# QSPI_NOR.net
KiCad netlist of a schematic drawn in Altium Designer
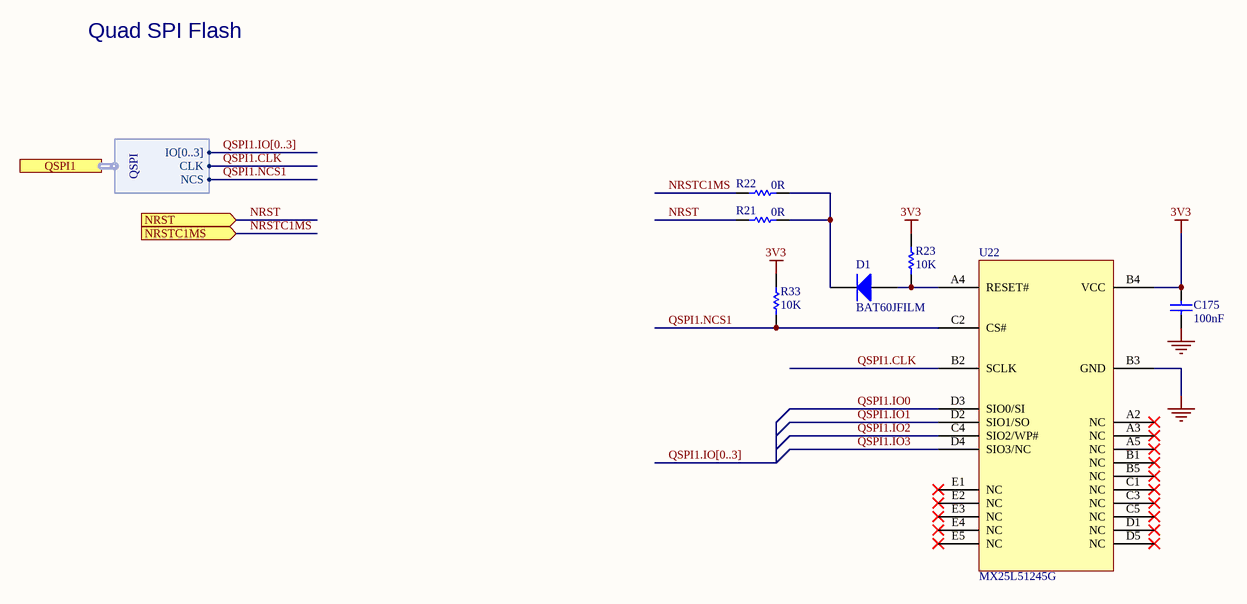
[diagram p0: QSPI_NOR.SchDoc]

(export (version "E")
  (design (tool "Eeschema 10.0.6"))
  (components
    (comp (ref "C175")
      (value "100nF")
      (footprint "MCD_PARTS:C0402")
      (description "Capacitor, MLCC, 100nF, 16V, X7R, +/-10%, 0402, T=0.5mm")
      (fields (field (name "INTERNAL_PART_NUMBER") "MCD-00006") (field (name "MANUFACTURER") "YAGEO"))
      (libsource (lib "MCD_PARTS_database") (part "Capacitor"))
    )
    (comp (ref "D1")
      (value "BAT60JFILM")
      (footprint "MCD_PARTS:DIO_SOD323")
      (fields
        (field (name "INTERNAL_PART_NUMBER") "MCD-00034")
        (field (name "BMS_PART_NUMBER") "9151097")
        (field (name "MANUFACTURER") "STMICROELECTRONICS")
      )
      (libsource (lib "MCD_PARTS_database") (part "BAT60JFILM"))
    )
    (comp (ref "R21")
      (value "0R")
      (footprint "MCD_PARTS:R0402")
      (description "Resistor,0R,0402,5%,1/16W")
      (fields
        (field (name "INTERNAL_PART_NUMBER") "MCD-00052")
        (field (name "MANUFACTURER_PART_NUMBER") "RC0402JR-070RL")
      )
      (libsource (lib "MCD_PARTS_database") (part "Resistor"))
    )
    (comp (ref "R22")
      (value "0R")
      (footprint "MCD_PARTS:R0402")
      (description "Resistor,0R,0402,5%,1/16W")
      (fields
        (field (name "INTERNAL_PART_NUMBER") "MCD-00052")
        (field (name "MANUFACTURER_PART_NUMBER") "RC0402JR-070RL")
      )
      (libsource (lib "MCD_PARTS_database") (part "Resistor"))
    )
    (comp (ref "R23")
      (value "10K")
      (footprint "MCD_PARTS:R0402")
      (description "Resistor,10K,0402,1%,1/16W")
      (fields
        (field (name "INTERNAL_PART_NUMBER") "MCD-00053")
        (field (name "MANUFACTURER_PART_NUMBER") "RC0402FR-0710KL")
        (field (name "PROVIDED_BY") "SUBCO")
      )
      (libsource (lib "MCD_PARTS_database") (part "Resistor"))
    )
    (comp (ref "R33")
      (value "10K")
      (footprint "MCD_PARTS:R0402")
      (description "Resistor,10K,0402,1%,1/16W")
      (fields
        (field (name "INTERNAL_PART_NUMBER") "MCD-00053")
        (field (name "MANUFACTURER_PART_NUMBER") "RC0402FR-0710KL")
        (field (name "PROVIDED_BY") "SUBCO")
      )
      (libsource (lib "MCD_PARTS_database") (part "Resistor"))
    )
    (comp (ref "U22")
      (value "MX25L51245G")
      (footprint "MCD_PARTS:ICC_BGA24_5X5-BALL-ARRAY_6X8_P1")
      (description "Memory,Serial-NOR,512Mb,3V")
      (fields
        (field (name "INTERNAL_PART_NUMBER") "MCD-00114")
        (field (name "MANUFACTURER") "MACRONIX")
        (field (name "PROVIDED_BY") "SUBCO")
      )
      (libsource (lib "MCD_PARTS_database") (part "MX25L51245G"))
    )
  )
  (nets
    (net (code "2") (name "/NRST") (class "Default")
      (node (ref "R21") (pin "1") (pinfunction "1_1") (pintype "passive"))
    )
    (net (code "3") (name "/NRSTC1MS") (class "Default")
      (node (ref "R22") (pin "1") (pinfunction "1_1") (pintype "passive"))
    )
    (net (code "4") (name "/QSPI1.CLK") (class "Default")
      (node (ref "U22") (pin "B2") (pinfunction "SCLK_B2") (pintype "passive"))
    )
    (net (code "5") (name "/QSPI1.IO0") (class "Default")
      (node (ref "U22") (pin "D3") (pinfunction "SIO0/SI_D3") (pintype "passive"))
    )
    (net (code "6") (name "/QSPI1.IO1") (class "Default")
      (node (ref "U22") (pin "D2") (pinfunction "SIO1/SO_D2") (pintype "passive"))
    )
    (net (code "7") (name "/QSPI1.IO2") (class "Default")
      (node (ref "U22") (pin "C4") (pinfunction "SIO2/WP#_C4") (pintype "passive"))
    )
    (net (code "8") (name "/QSPI1.IO3") (class "Default")
      (node (ref "U22") (pin "D4") (pinfunction "SIO3/NC_D4") (pintype "passive"))
    )
    (net (code "10") (name "/QSPI1.NCS1") (class "Default")
      (node (ref "R33") (pin "1") (pinfunction "1_1") (pintype "passive"))
      (node (ref "U22") (pin "C2") (pinfunction "CS#_C2") (pintype "passive"))
    )
    (net (code "12") (name "3V3") (class "Default")
      (node (ref "C175") (pin "2") (pinfunction "2_2") (pintype "passive"))
      (node (ref "R23") (pin "2") (pinfunction "2_2") (pintype "passive"))
      (node (ref "R33") (pin "2") (pinfunction "2_2") (pintype "passive"))
      (node (ref "U22") (pin "B4") (pinfunction "VCC_B4") (pintype "passive"))
    )
    (net (code "13") (name "GND") (class "Default")
      (node (ref "C175") (pin "1") (pinfunction "1_1") (pintype "passive"))
      (node (ref "U22") (pin "B3") (pinfunction "GND_B3") (pintype "passive"))
    )
    (net (code "14") (name "Net-(D1-A)") (class "Default")
      (node (ref "D1") (pin "1") (pinfunction "A_1") (pintype "passive"))
      (node (ref "R23") (pin "1") (pinfunction "1_1") (pintype "passive"))
      (node (ref "U22") (pin "A4") (pinfunction "RESET#_A4") (pintype "passive"))
    )
    (net (code "15") (name "Net-(D1-K)") (class "Default")
      (node (ref "D1") (pin "2") (pinfunction "K_2") (pintype "passive"))
      (node (ref "R21") (pin "2") (pinfunction "2_2") (pintype "passive"))
      (node (ref "R22") (pin "2") (pinfunction "2_2") (pintype "passive"))
    )
    (net (code "16") (name "unconnected-(U22-NC-PadA2)") (class "Default")
      (node (ref "U22") (pin "A2") (pinfunction "NC_A2") (pintype "passive+no_connect"))
    )
    (net (code "17") (name "unconnected-(U22-NC-PadA3)") (class "Default")
      (node (ref "U22") (pin "A3") (pinfunction "NC_A3") (pintype "passive+no_connect"))
    )
    (net (code "18") (name "unconnected-(U22-NC-PadA5)") (class "Default")
      (node (ref "U22") (pin "A5") (pinfunction "NC_A5") (pintype "passive+no_connect"))
    )
    (net (code "19") (name "unconnected-(U22-NC-PadB1)") (class "Default")
      (node (ref "U22") (pin "B1") (pinfunction "NC_B1") (pintype "passive+no_connect"))
    )
    (net (code "20") (name "unconnected-(U22-NC-PadB5)") (class "Default")
      (node (ref "U22") (pin "B5") (pinfunction "NC_B5") (pintype "passive+no_connect"))
    )
    (net (code "21") (name "unconnected-(U22-NC-PadC1)") (class "Default")
      (node (ref "U22") (pin "C1") (pinfunction "NC_C1") (pintype "passive+no_connect"))
    )
    (net (code "22") (name "unconnected-(U22-NC-PadC3)") (class "Default")
      (node (ref "U22") (pin "C3") (pinfunction "NC_C3") (pintype "passive+no_connect"))
    )
    (net (code "23") (name "unconnected-(U22-NC-PadC5)") (class "Default")
      (node (ref "U22") (pin "C5") (pinfunction "NC_C5") (pintype "passive+no_connect"))
    )
    (net (code "24") (name "unconnected-(U22-NC-PadD1)") (class "Default")
      (node (ref "U22") (pin "D1") (pinfunction "NC_D1") (pintype "passive+no_connect"))
    )
    (net (code "25") (name "unconnected-(U22-NC-PadD5)") (class "Default")
      (node (ref "U22") (pin "D5") (pinfunction "NC_D5") (pintype "passive+no_connect"))
    )
    (net (code "26") (name "unconnected-(U22-NC-PadE1)") (class "Default")
      (node (ref "U22") (pin "E1") (pinfunction "NC_E1") (pintype "passive+no_connect"))
    )
    (net (code "27") (name "unconnected-(U22-NC-PadE2)") (class "Default")
      (node (ref "U22") (pin "E2") (pinfunction "NC_E2") (pintype "passive+no_connect"))
    )
    (net (code "28") (name "unconnected-(U22-NC-PadE3)") (class "Default")
      (node (ref "U22") (pin "E3") (pinfunction "NC_E3") (pintype "passive+no_connect"))
    )
    (net (code "29") (name "unconnected-(U22-NC-PadE4)") (class "Default")
      (node (ref "U22") (pin "E4") (pinfunction "NC_E4") (pintype "passive+no_connect"))
    )
    (net (code "30") (name "unconnected-(U22-NC-PadE5)") (class "Default")
      (node (ref "U22") (pin "E5") (pinfunction "NC_E5") (pintype "passive+no_connect"))
    )
  )
)
